# design.net
KiCad netlist of a schematic drawn in Altium Designer
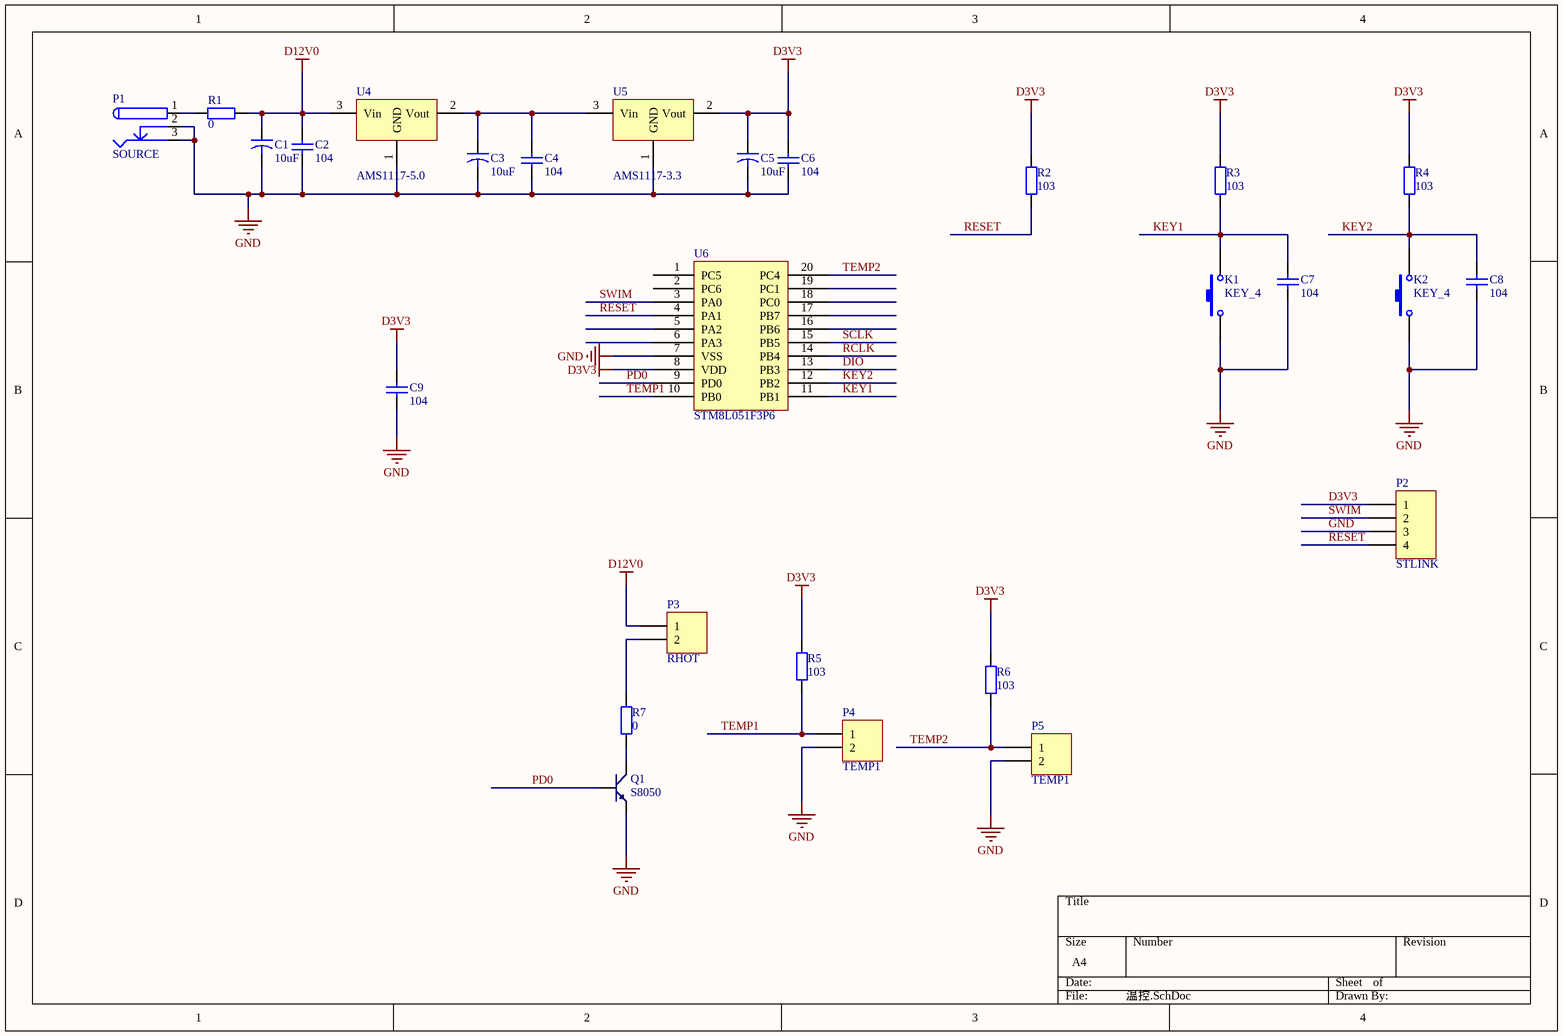
[diagram p0: 温控.SchDoc]

(export (version "E")
  (design (tool "Eeschema 10.0.6"))
  (components
    (comp (ref "C1")
      (value "CAP")
      (footprint "A_3216")
      (fields (field (name "VAULE") "10uF"))
      (libsource (lib "DX") (part "CAP2"))
    )
    (comp (ref "C2")
      (value "104")
      (footprint "0603_cap")
      (description "Capacitor")
      (fields (field (name "Comment") "Cap") (field (name "PUBLISHER") "Altium Limited"))
      (libsource (lib "DX") (part "Cap"))
    )
    (comp (ref "C3")
      (value "CAP")
      (footprint "A_3216")
      (fields (field (name "VAULE") "10uF"))
      (libsource (lib "DX") (part "CAP2"))
    )
    (comp (ref "C4")
      (value "104")
      (footprint "0603_cap")
      (description "Capacitor")
      (fields (field (name "Comment") "Cap") (field (name "PUBLISHER") "Altium Limited"))
      (libsource (lib "DX") (part "Cap"))
    )
    (comp (ref "C5")
      (value "CAP")
      (footprint "A_3216")
      (fields (field (name "VAULE") "10uF"))
      (libsource (lib "DX") (part "CAP2"))
    )
    (comp (ref "C6")
      (value "104")
      (footprint "0603_cap")
      (description "Capacitor")
      (fields (field (name "Comment") "Cap") (field (name "PUBLISHER") "Altium Limited"))
      (libsource (lib "DX") (part "Cap"))
    )
    (comp (ref "C7")
      (value "104")
      (footprint "0603_cap")
      (description "Capacitor")
      (fields (field (name "Comment") "Cap") (field (name "PUBLISHER") "Altium Limited"))
      (libsource (lib "DX") (part "Cap"))
    )
    (comp (ref "C8")
      (value "104")
      (footprint "0603_cap")
      (description "Capacitor")
      (fields (field (name "Comment") "Cap") (field (name "PUBLISHER") "Altium Limited"))
      (libsource (lib "DX") (part "Cap"))
    )
    (comp (ref "C9")
      (value "104")
      (footprint "0603_cap")
      (description "Capacitor")
      (fields (field (name "Comment") "Cap") (field (name "PUBLISHER") "Altium Limited"))
      (libsource (lib "DX") (part "Cap"))
    )
    (comp (ref "K1")
      (value "KEY_4")
      (footprint "KEY6*6")
      (description "Switch")
      (fields (field (name "PUBLISHER") "Altium Limited"))
      (libsource (lib "DX") (part "KEY_4"))
    )
    (comp (ref "K2")
      (value "KEY_4")
      (footprint "KEY6*6")
      (description "Switch")
      (fields (field (name "PUBLISHER") "Altium Limited"))
      (libsource (lib "DX") (part "KEY_4"))
    )
    (comp (ref "P1")
      (value "SOURCE")
      (footprint "source")
      (fields (field (name "PUBLISHER") "Altium Limited"))
      (libsource (lib "DX") (part "SOURCE"))
    )
    (comp (ref "P2")
      (value "STLINK")
      (footprint "HDR1X4")
      (description "Header, 4-Pin")
      (fields (field (name "PUBLISHER") "Altium Limited"))
      (libsource (lib "Miscellaneous Connectors") (part "Header 4"))
    )
    (comp (ref "P3")
      (value "RHOT")
      (footprint "HDR1X2")
      (description "Header, 2-Pin")
      (fields (field (name "PUBLISHER") "Altium Limited"))
      (libsource (lib "WarShip+V3+STM32103封装库") (part "Header 2"))
    )
    (comp (ref "P4")
      (value "TEMP1")
      (footprint "HDR1X2")
      (description "Header, 2-Pin")
      (fields (field (name "PUBLISHER") "Altium Limited"))
      (libsource (lib "WarShip+V3+STM32103封装库") (part "Header 2"))
    )
    (comp (ref "P5")
      (value "TEMP1")
      (footprint "HDR1X2")
      (description "Header, 2-Pin")
      (fields (field (name "PUBLISHER") "Altium Limited"))
      (libsource (lib "WarShip+V3+STM32103封装库") (part "Header 2"))
    )
    (comp (ref "Q1")
      (value "S8050")
      (footprint "SOT-23R")
      (description "8050/BCW846/BCW847")
      (libsource (lib "WarShip+V3+STM32103封装库") (part "NPN"))
    )
    (comp (ref "R1")
      (value "0")
      (footprint "1206")
      (description "Resistor")
      (fields (field (name "PUBLISHER") "Altium Limited"))
      (libsource (lib "") (part "RES_1"))
    )
    (comp (ref "R2")
      (value "103")
      (footprint "0603")
      (description "Resistor")
      (fields (field (name "PUBLISHER") "Altium Limited"))
      (libsource (lib "DX") (part "RES"))
    )
    (comp (ref "R3")
      (value "103")
      (footprint "0603")
      (description "Resistor")
      (fields (field (name "PUBLISHER") "Altium Limited"))
      (libsource (lib "DX") (part "RES"))
    )
    (comp (ref "R4")
      (value "103")
      (footprint "0603")
      (description "Resistor")
      (fields (field (name "PUBLISHER") "Altium Limited"))
      (libsource (lib "DX") (part "RES"))
    )
    (comp (ref "R5")
      (value "103")
      (footprint "0603")
      (description "Resistor")
      (fields (field (name "PUBLISHER") "Altium Limited"))
      (libsource (lib "DX") (part "RES"))
    )
    (comp (ref "R6")
      (value "103")
      (footprint "0603")
      (description "Resistor")
      (fields (field (name "PUBLISHER") "Altium Limited"))
      (libsource (lib "DX") (part "RES"))
    )
    (comp (ref "R7")
      (value "0")
      (footprint "0603")
      (description "Resistor")
      (fields (field (name "PUBLISHER") "Altium Limited"))
      (libsource (lib "DX") (part "RES"))
    )
    (comp (ref "U4")
      (value "AMS1117-5.0")
      (footprint "SOT223")
      (description "3.3V电压转换器AMS1117")
      (libsource (lib "DX") (part "AMS1117"))
    )
    (comp (ref "U5")
      (value "AMS1117-3.3")
      (footprint "SOT223")
      (description "3.3V电压转换器AMS1117")
      (libsource (lib "DX") (part "AMS1117"))
    )
    (comp (ref "U6")
      (value "STM8L051F3P6")
      (footprint "LC-TSSOP-20")
      (libsource (lib "DX") (part "STM8L051F3P6"))
    )
  )
  (nets
    (net (code "1") (name "/DIO") (class "Default")
      (node (ref "U6") (pin "13") (pinfunction "PB3_13") (pintype "passive"))
    )
    (net (code "2") (name "/KEY1") (class "Default")
      (node (ref "C7") (pin "2") (pinfunction "2_2") (pintype "passive"))
      (node (ref "K1") (pin "2") (pinfunction "2_2") (pintype "passive"))
      (node (ref "R3") (pin "1") (pinfunction "1_1") (pintype "passive"))
      (node (ref "U6") (pin "11") (pinfunction "PB1_11") (pintype "passive"))
    )
    (net (code "3") (name "/KEY2") (class "Default")
      (node (ref "C8") (pin "2") (pinfunction "2_2") (pintype "passive"))
      (node (ref "K2") (pin "2") (pinfunction "2_2") (pintype "passive"))
      (node (ref "R4") (pin "1") (pinfunction "1_1") (pintype "passive"))
      (node (ref "U6") (pin "12") (pinfunction "PB2_12") (pintype "passive"))
    )
    (net (code "4") (name "/PD0") (class "Default")
      (node (ref "Q1") (pin "2") (pinfunction "B_2") (pintype "passive"))
      (node (ref "U6") (pin "9") (pinfunction "PD0_9") (pintype "passive"))
    )
    (net (code "5") (name "/RCLK") (class "Default")
      (node (ref "U6") (pin "14") (pinfunction "PB4_14") (pintype "passive"))
    )
    (net (code "6") (name "/RESET") (class "Default")
      (node (ref "P2") (pin "4") (pinfunction "4_4") (pintype "passive"))
      (node (ref "R2") (pin "1") (pinfunction "1_1") (pintype "passive"))
      (node (ref "U6") (pin "4") (pinfunction "PA1_4") (pintype "passive"))
    )
    (net (code "7") (name "/SCLK") (class "Default")
      (node (ref "U6") (pin "15") (pinfunction "PB5_15") (pintype "passive"))
    )
    (net (code "8") (name "/SWIM") (class "Default")
      (node (ref "P2") (pin "2") (pinfunction "2_2") (pintype "passive"))
      (node (ref "U6") (pin "3") (pinfunction "PA0_3") (pintype "passive"))
    )
    (net (code "9") (name "/TEMP1") (class "Default")
      (node (ref "P4") (pin "1") (pinfunction "1_1") (pintype "passive"))
      (node (ref "R5") (pin "1") (pinfunction "1_1") (pintype "passive"))
      (node (ref "U6") (pin "10") (pinfunction "PB0_10") (pintype "passive"))
    )
    (net (code "10") (name "/TEMP2") (class "Default")
      (node (ref "P5") (pin "1") (pinfunction "1_1") (pintype "passive"))
      (node (ref "R6") (pin "1") (pinfunction "1_1") (pintype "passive"))
      (node (ref "U6") (pin "20") (pinfunction "PC4_20") (pintype "passive"))
    )
    (net (code "11") (name "D3V3") (class "Default")
      (node (ref "C5") (pin "1") (pinfunction "1_1") (pintype "passive"))
      (node (ref "C6") (pin "2") (pinfunction "2_2") (pintype "passive"))
      (node (ref "C9") (pin "2") (pinfunction "2_2") (pintype "passive"))
      (node (ref "P2") (pin "1") (pinfunction "1_1") (pintype "passive"))
      (node (ref "R2") (pin "2") (pinfunction "2_2") (pintype "passive"))
      (node (ref "R3") (pin "2") (pinfunction "2_2") (pintype "passive"))
      (node (ref "R4") (pin "2") (pinfunction "2_2") (pintype "passive"))
      (node (ref "R5") (pin "2") (pinfunction "2_2") (pintype "passive"))
      (node (ref "R6") (pin "2") (pinfunction "2_2") (pintype "passive"))
      (node (ref "U5") (pin "2") (pinfunction "Vout_2") (pintype "passive"))
      (node (ref "U6") (pin "8") (pinfunction "VDD_8") (pintype "passive"))
    )
    (net (code "12") (name "D12V0") (class "Default")
      (node (ref "C1") (pin "1") (pinfunction "1_1") (pintype "passive"))
      (node (ref "C2") (pin "2") (pinfunction "2_2") (pintype "passive"))
      (node (ref "P3") (pin "1") (pinfunction "1_1") (pintype "passive"))
      (node (ref "R1") (pin "2") (pinfunction "2_2") (pintype "passive"))
      (node (ref "U4") (pin "3") (pinfunction "Vin_3") (pintype "passive"))
    )
    (net (code "13") (name "GND") (class "Default")
      (node (ref "C1") (pin "2") (pinfunction "2_2") (pintype "passive"))
      (node (ref "C2") (pin "1") (pinfunction "1_1") (pintype "passive"))
      (node (ref "C3") (pin "2") (pinfunction "2_2") (pintype "passive"))
      (node (ref "C4") (pin "1") (pinfunction "1_1") (pintype "passive"))
      (node (ref "C5") (pin "2") (pinfunction "2_2") (pintype "passive"))
      (node (ref "C6") (pin "1") (pinfunction "1_1") (pintype "passive"))
      (node (ref "C7") (pin "1") (pinfunction "1_1") (pintype "passive"))
      (node (ref "C8") (pin "1") (pinfunction "1_1") (pintype "passive"))
      (node (ref "C9") (pin "1") (pinfunction "1_1") (pintype "passive"))
      (node (ref "K1") (pin "1") (pinfunction "1_1") (pintype "passive"))
      (node (ref "K2") (pin "1") (pinfunction "1_1") (pintype "passive"))
      (node (ref "P1") (pin "2") (pinfunction "2_2") (pintype "power_in"))
      (node (ref "P1") (pin "3") (pinfunction "3_3") (pintype "power_in"))
      (node (ref "P2") (pin "3") (pinfunction "3_3") (pintype "passive"))
      (node (ref "P4") (pin "2") (pinfunction "2_2") (pintype "passive"))
      (node (ref "P5") (pin "2") (pinfunction "2_2") (pintype "passive"))
      (node (ref "Q1") (pin "1") (pinfunction "E_1") (pintype "passive"))
      (node (ref "U4") (pin "1") (pinfunction "GND_1") (pintype "passive"))
      (node (ref "U5") (pin "1") (pinfunction "GND_1") (pintype "passive"))
      (node (ref "U6") (pin "7") (pinfunction "VSS_7") (pintype "passive"))
    )
    (net (code "14") (name "Net-(P1-Pad1)") (class "Default")
      (node (ref "P1") (pin "1") (pinfunction "1_1") (pintype "power_in"))
      (node (ref "R1") (pin "1") (pinfunction "1_1") (pintype "passive"))
    )
    (net (code "15") (name "Net-(P3-Pad2)") (class "Default")
      (node (ref "P3") (pin "2") (pinfunction "2_2") (pintype "passive"))
      (node (ref "R7") (pin "2") (pinfunction "2_2") (pintype "passive"))
    )
    (net (code "16") (name "Net-(Q1-C)") (class "Default")
      (node (ref "Q1") (pin "3") (pinfunction "C_3") (pintype "passive"))
      (node (ref "R7") (pin "1") (pinfunction "1_1") (pintype "passive"))
    )
    (net (code "17") (name "Net-(U4-Vout)") (class "Default")
      (node (ref "C3") (pin "1") (pinfunction "1_1") (pintype "passive"))
      (node (ref "C4") (pin "2") (pinfunction "2_2") (pintype "passive"))
      (node (ref "U4") (pin "2") (pinfunction "Vout_2") (pintype "passive"))
      (node (ref "U5") (pin "3") (pinfunction "Vin_3") (pintype "passive"))
    )
    (net (code "18") (name "unconnected-(U6-PA2-Pad5)") (class "Default")
      (node (ref "U6") (pin "5") (pinfunction "PA2_5") (pintype "passive"))
    )
    (net (code "19") (name "unconnected-(U6-PA3-Pad6)") (class "Default")
      (node (ref "U6") (pin "6") (pinfunction "PA3_6") (pintype "passive"))
    )
    (net (code "20") (name "unconnected-(U6-PB6-Pad16)") (class "Default")
      (node (ref "U6") (pin "16") (pinfunction "PB6_16") (pintype "passive"))
    )
    (net (code "21") (name "unconnected-(U6-PB7-Pad17)") (class "Default")
      (node (ref "U6") (pin "17") (pinfunction "PB7_17") (pintype "passive"))
    )
    (net (code "22") (name "unconnected-(U6-PC0-Pad18)") (class "Default")
      (node (ref "U6") (pin "18") (pinfunction "PC0_18") (pintype "passive"))
    )
    (net (code "23") (name "unconnected-(U6-PC1-Pad19)") (class "Default")
      (node (ref "U6") (pin "19") (pinfunction "PC1_19") (pintype "passive"))
    )
    (net (code "24") (name "unconnected-(U6-PC5-Pad1)") (class "Default")
      (node (ref "U6") (pin "1") (pinfunction "PC5_1") (pintype "passive"))
    )
    (net (code "25") (name "unconnected-(U6-PC6-Pad2)") (class "Default")
      (node (ref "U6") (pin "2") (pinfunction "PC6_2") (pintype "passive"))
    )
  )
)
